# dp_linistepper_v1_0.net
KiCad netlist of a schematic drawn in EAGLE
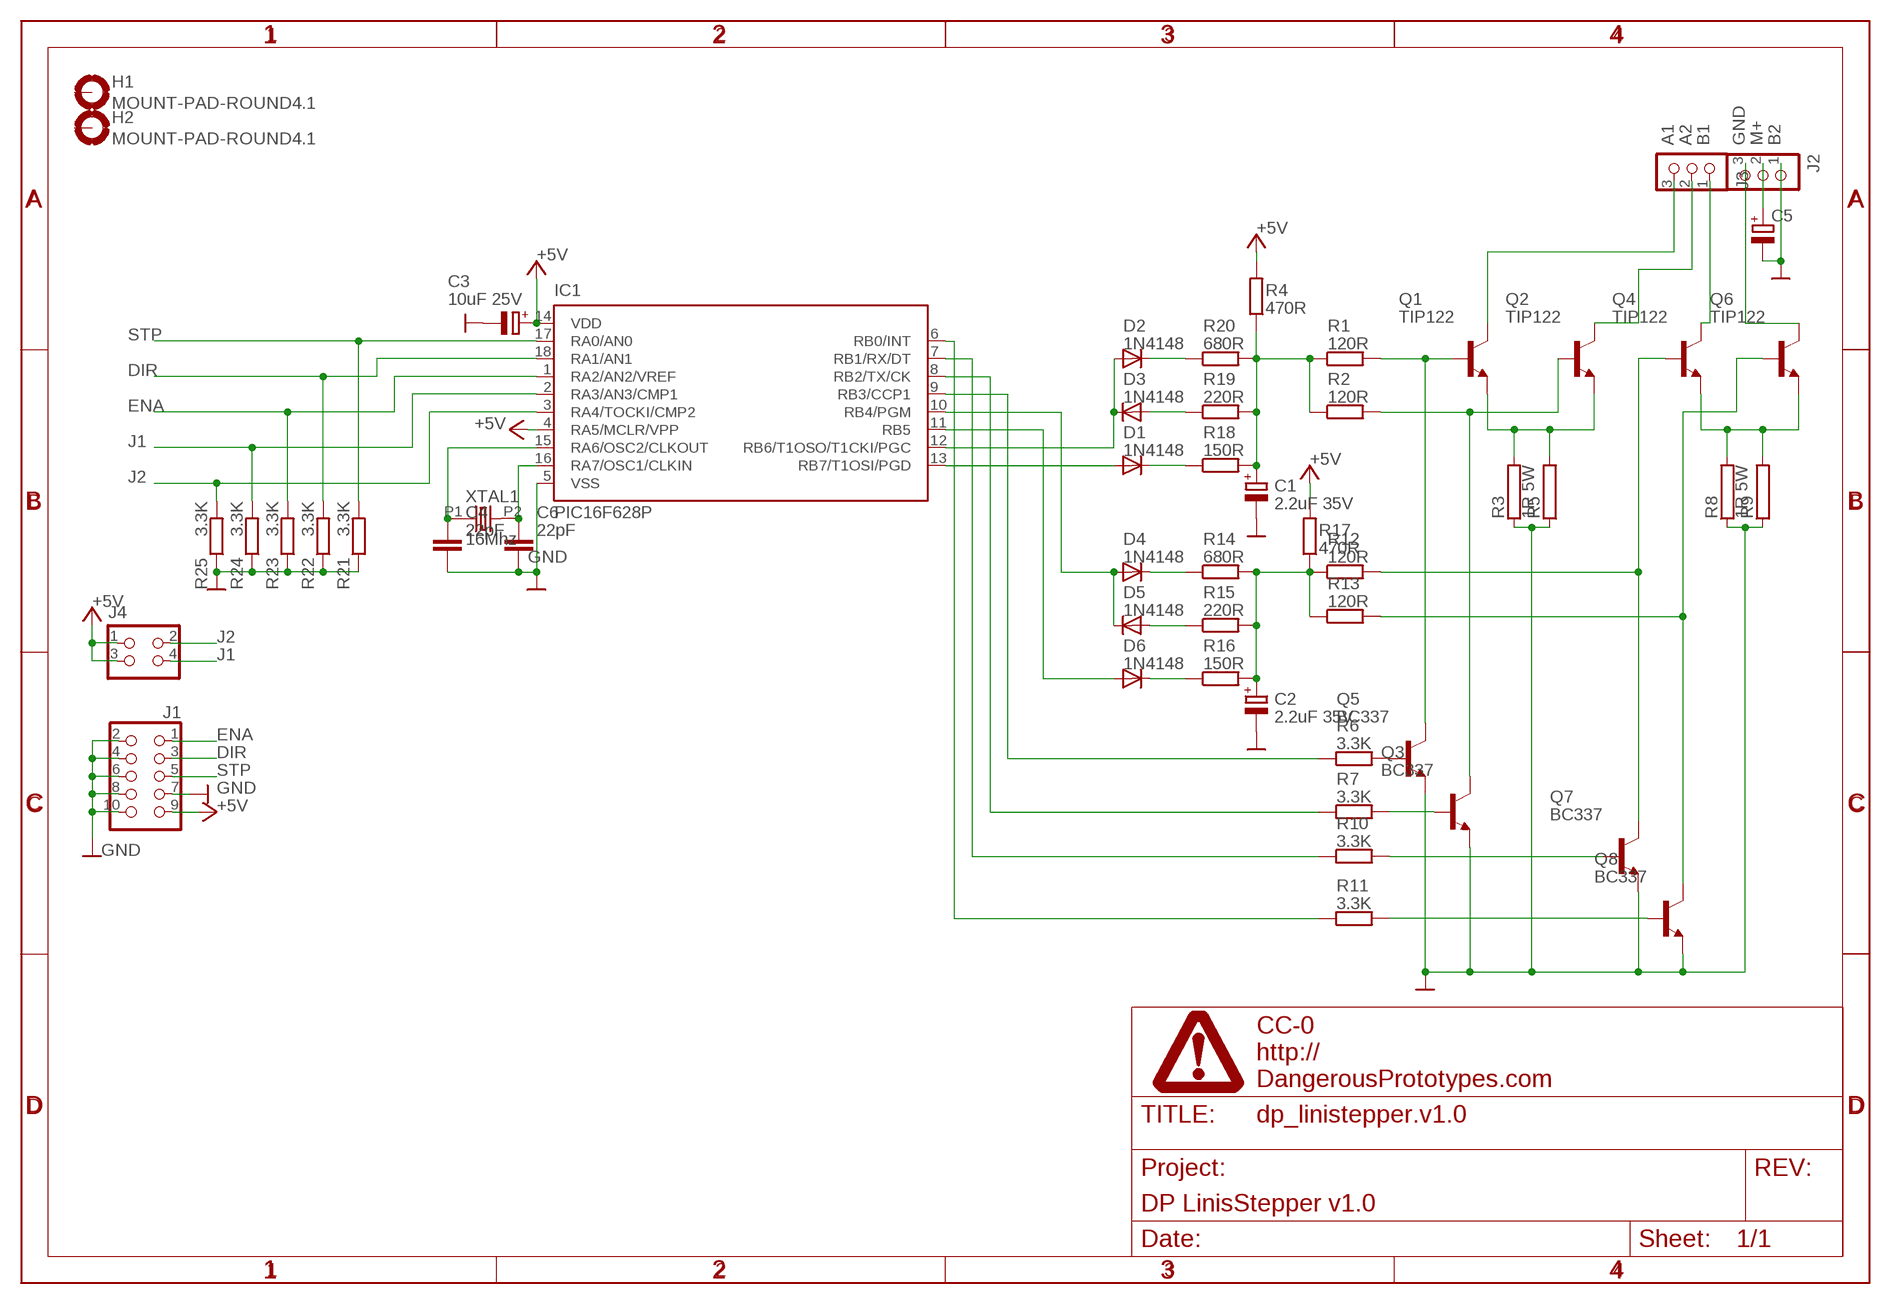
[diagram p0: schematic, sheet 1]

(export (version "E")
  (design (tool "Eeschema 10.0.6"))
  (components
    (comp (ref "C1")
      (value "2.2uF 35V")
      (footprint "eagle-import:ETR1")
      (libsource (lib "eagle-import") (part "CPOL-EUETR1"))
    )
    (comp (ref "C2")
      (value "2.2uF 35V")
      (footprint "eagle-import:ETR1")
      (libsource (lib "eagle-import") (part "CPOL-EUETR1"))
    )
    (comp (ref "C3")
      (value "10uF 25V")
      (footprint "eagle-import:ETR1")
      (libsource (lib "eagle-import") (part "CPOL-EUETR1"))
    )
    (comp (ref "C4")
      (value "22pF")
      (footprint "eagle-import:C0.1PTH")
      (libsource (lib "eagle-import") (part "CAPACITOR_NPOL-PTH_0.1{dblquote}"))
    )
    (comp (ref "C5")
      (value "CPOL-EUE5-13")
      (footprint "eagle-import:E5-13")
      (libsource (lib "eagle-import") (part "CPOL-EUE5-13"))
    )
    (comp (ref "C6")
      (value "22pF")
      (footprint "eagle-import:C0.1PTH")
      (libsource (lib "eagle-import") (part "CAPACITOR_NPOL-PTH_0.1{dblquote}"))
    )
    (comp (ref "D1")
      (value "1N4148")
      (footprint "eagle-import:DO35-10")
      (libsource (lib "eagle-import") (part "1N4148"))
    )
    (comp (ref "D2")
      (value "1N4148")
      (footprint "eagle-import:DO35-10")
      (libsource (lib "eagle-import") (part "1N4148"))
    )
    (comp (ref "D3")
      (value "1N4148")
      (footprint "eagle-import:DO35-10")
      (libsource (lib "eagle-import") (part "1N4148"))
    )
    (comp (ref "D4")
      (value "1N4148")
      (footprint "eagle-import:DO35-10")
      (libsource (lib "eagle-import") (part "1N4148"))
    )
    (comp (ref "D5")
      (value "1N4148")
      (footprint "eagle-import:DO35-10")
      (libsource (lib "eagle-import") (part "1N4148"))
    )
    (comp (ref "D6")
      (value "1N4148")
      (footprint "eagle-import:DO35-10")
      (libsource (lib "eagle-import") (part "1N4148"))
    )
    (comp (ref "H1")
      (value "MOUNT-PAD-ROUND4.1")
      (footprint "eagle-import:4,1-PAD")
      (libsource (lib "eagle-import") (part "MOUNT-PAD-ROUND4.1"))
    )
    (comp (ref "H2")
      (value "MOUNT-PAD-ROUND4.1")
      (footprint "eagle-import:4,1-PAD")
      (libsource (lib "eagle-import") (part "MOUNT-PAD-ROUND4.1"))
    )
    (comp (ref "IC1")
      (value "PIC16F628P")
      (footprint "eagle-import:DIL18")
      (fields (field (name "MF") "MICROCHIP") (field (name "MPN") "PIC16F628-04I/P"))
      (libsource (lib "eagle-import") (part "PIC16F62P8"))
    )
    (comp (ref "J1")
      (value "CON_HEADER_2X05-PTH")
      (footprint "eagle-import:M2X5")
      (libsource (lib "eagle-import") (part "CON_HEADER_2X05-PTH"))
    )
    (comp (ref "J2")
      (value "CON_TERMINAL_BLOCK_03-5MM")
      (footprint "eagle-import:TERMINAL_BLOCK_3P_5")
      (libsource (lib "eagle-import") (part "CON_TERMINAL_BLOCK_03-5MM"))
    )
    (comp (ref "J3")
      (value "CON_TERMINAL_BLOCK_03-5MM")
      (footprint "eagle-import:TERMINAL_BLOCK_3P_5")
      (libsource (lib "eagle-import") (part "CON_TERMINAL_BLOCK_03-5MM"))
    )
    (comp (ref "J4")
      (value "CON_HEADER_2X02-PTH")
      (footprint "eagle-import:M2X2")
      (libsource (lib "eagle-import") (part "CON_HEADER_2X02-PTH"))
    )
    (comp (ref "Q1")
      (value "TIP122")
      (footprint "eagle-import:TO220AV")
      (libsource (lib "eagle-import") (part "2SC2098V"))
    )
    (comp (ref "Q2")
      (value "TIP122")
      (footprint "eagle-import:TO220AV")
      (libsource (lib "eagle-import") (part "2SC2098V"))
    )
    (comp (ref "Q3")
      (value "BC337")
      (footprint "eagle-import:TO92")
      (libsource (lib "eagle-import") (part "BC337"))
    )
    (comp (ref "Q4")
      (value "TIP122")
      (footprint "eagle-import:TO220AV")
      (libsource (lib "eagle-import") (part "2SC2098V"))
    )
    (comp (ref "Q5")
      (value "BC337")
      (footprint "eagle-import:TO92")
      (libsource (lib "eagle-import") (part "BC337"))
    )
    (comp (ref "Q6")
      (value "TIP122")
      (footprint "eagle-import:TO220AV")
      (libsource (lib "eagle-import") (part "2SC2098V"))
    )
    (comp (ref "Q7")
      (value "BC337")
      (footprint "eagle-import:TO92")
      (libsource (lib "eagle-import") (part "BC337"))
    )
    (comp (ref "Q8")
      (value "BC337")
      (footprint "eagle-import:TO92")
      (libsource (lib "eagle-import") (part "BC337"))
    )
    (comp (ref "R1")
      (value "120R")
      (footprint "eagle-import:RTH025W")
      (libsource (lib "eagle-import") (part "RESISTOR-PTH-0.4"))
    )
    (comp (ref "R2")
      (value "120R")
      (footprint "eagle-import:RTH025W")
      (libsource (lib "eagle-import") (part "RESISTOR-PTH-0.4"))
    )
    (comp (ref "R3")
      (value "1R 5W")
      (footprint "eagle-import:HPS923")
      (libsource (lib "eagle-import") (part "RHPS923"))
    )
    (comp (ref "R4")
      (value "470R")
      (footprint "eagle-import:RTH025W")
      (libsource (lib "eagle-import") (part "RESISTOR-PTH-0.4"))
    )
    (comp (ref "R5")
      (value "RHPS63")
      (footprint "eagle-import:HPS63")
      (libsource (lib "eagle-import") (part "RHPS63"))
    )
    (comp (ref "R6")
      (value "3.3K")
      (footprint "eagle-import:RTH025W")
      (libsource (lib "eagle-import") (part "RESISTOR-PTH-0.4"))
    )
    (comp (ref "R7")
      (value "3.3K")
      (footprint "eagle-import:RTH025W")
      (libsource (lib "eagle-import") (part "RESISTOR-PTH-0.4"))
    )
    (comp (ref "R8")
      (value "1R 5W")
      (footprint "eagle-import:HPS923")
      (fields (field (name "OC_FARNELL") "unknown") (field (name "OC_NEWARK") "unknown"))
      (libsource (lib "eagle-import") (part "RHPS923"))
    )
    (comp (ref "R9")
      (value "RHPS63")
      (footprint "eagle-import:HPS63")
      (fields (field (name "OC_FARNELL") "unknown") (field (name "OC_NEWARK") "unknown"))
      (libsource (lib "eagle-import") (part "RHPS63"))
    )
    (comp (ref "R10")
      (value "3.3K")
      (footprint "eagle-import:RTH025W")
      (libsource (lib "eagle-import") (part "RESISTOR-PTH-0.4"))
    )
    (comp (ref "R11")
      (value "3.3K")
      (footprint "eagle-import:RTH025W")
      (libsource (lib "eagle-import") (part "RESISTOR-PTH-0.4"))
    )
    (comp (ref "R12")
      (value "120R")
      (footprint "eagle-import:RTH025W")
      (libsource (lib "eagle-import") (part "RESISTOR-PTH-0.4"))
    )
    (comp (ref "R13")
      (value "120R")
      (footprint "eagle-import:RTH025W")
      (libsource (lib "eagle-import") (part "RESISTOR-PTH-0.4"))
    )
    (comp (ref "R14")
      (value "680R")
      (footprint "eagle-import:RTH025W")
      (libsource (lib "eagle-import") (part "RESISTOR-PTH-0.4"))
    )
    (comp (ref "R15")
      (value "220R")
      (footprint "eagle-import:RTH025W")
      (libsource (lib "eagle-import") (part "RESISTOR-PTH-0.4"))
    )
    (comp (ref "R16")
      (value "150R")
      (footprint "eagle-import:RTH025W")
      (libsource (lib "eagle-import") (part "RESISTOR-PTH-0.4"))
    )
    (comp (ref "R17")
      (value "470R")
      (footprint "eagle-import:RTH025W")
      (libsource (lib "eagle-import") (part "RESISTOR-PTH-0.4"))
    )
    (comp (ref "R18")
      (value "150R")
      (footprint "eagle-import:RTH025W")
      (libsource (lib "eagle-import") (part "RESISTOR-PTH-0.4"))
    )
    (comp (ref "R19")
      (value "220R")
      (footprint "eagle-import:RTH025W")
      (libsource (lib "eagle-import") (part "RESISTOR-PTH-0.4"))
    )
    (comp (ref "R20")
      (value "680R")
      (footprint "eagle-import:RTH025W")
      (libsource (lib "eagle-import") (part "RESISTOR-PTH-0.4"))
    )
    (comp (ref "R21")
      (value "3.3K")
      (footprint "eagle-import:RTH025W")
      (libsource (lib "eagle-import") (part "RESISTOR-PTH-0.4"))
    )
    (comp (ref "R22")
      (value "3.3K")
      (footprint "eagle-import:RTH025W")
      (libsource (lib "eagle-import") (part "RESISTOR-PTH-0.4"))
    )
    (comp (ref "R23")
      (value "3.3K")
      (footprint "eagle-import:RTH025W")
      (libsource (lib "eagle-import") (part "RESISTOR-PTH-0.4"))
    )
    (comp (ref "R24")
      (value "3.3K")
      (footprint "eagle-import:RTH025W")
      (libsource (lib "eagle-import") (part "RESISTOR-PTH-0.4"))
    )
    (comp (ref "R25")
      (value "3.3K")
      (footprint "eagle-import:RTH025W")
      (libsource (lib "eagle-import") (part "RESISTOR-PTH-0.4"))
    )
    (comp (ref "U$1")
      (value "FRAME_DINA4_L")
      (footprint "eagle-import:DP_LOGO")
      (fields (field (name "LICENSE") "CC-0") (field (name "PROJECT") "DP LinisStepper v1.0"))
      (libsource (lib "eagle-import") (part "FRAME_DINA4_L"))
    )
    (comp (ref "XTAL1")
      (value "16Mhz")
      (footprint "eagle-import:HC-49U-PTH")
      (libsource (lib "eagle-import") (part "OSC-XTAL-HC-49U-PTH"))
    )
  )
  (nets
    (net (code "1") (name "/A1") (class "Default")
      (node (ref "J3") (pin "3") (pinfunction "3_3") (pintype "bidirectional"))
      (node (ref "Q1") (pin "2") (pinfunction "C_2") (pintype "passive"))
    )
    (net (code "2") (name "/A2") (class "Default")
      (node (ref "J3") (pin "2") (pinfunction "2_2") (pintype "bidirectional"))
      (node (ref "Q2") (pin "2") (pinfunction "C_2") (pintype "passive"))
    )
    (net (code "3") (name "/B1") (class "Default")
      (node (ref "J3") (pin "1") (pinfunction "1_1") (pintype "bidirectional"))
      (node (ref "Q4") (pin "2") (pinfunction "C_2") (pintype "passive"))
    )
    (net (code "4") (name "/B2") (class "Default")
      (node (ref "J2") (pin "3") (pinfunction "3_3") (pintype "bidirectional"))
      (node (ref "Q6") (pin "2") (pinfunction "C_2") (pintype "passive"))
    )
    (net (code "5") (name "/DIR") (class "Default")
      (node (ref "IC1") (pin "18") (pinfunction "RA1/AN1_18") (pintype "bidirectional"))
      (node (ref "J1") (pin "3") (pinfunction "3_3") (pintype "passive"))
      (node (ref "R22") (pin "2") (pinfunction "2_2") (pintype "passive"))
    )
    (net (code "6") (name "/ENA") (class "Default")
      (node (ref "IC1") (pin "1") (pinfunction "RA2/AN2/VREF_1") (pintype "bidirectional"))
      (node (ref "J1") (pin "1") (pinfunction "1_1") (pintype "passive"))
      (node (ref "R23") (pin "2") (pinfunction "2_2") (pintype "passive"))
    )
    (net (code "7") (name "/J1") (class "Default")
      (node (ref "IC1") (pin "2") (pinfunction "RA3/AN3/CMP1_2") (pintype "bidirectional"))
      (node (ref "J4") (pin "4") (pinfunction "4_4") (pintype "passive"))
      (node (ref "R24") (pin "2") (pinfunction "2_2") (pintype "passive"))
    )
    (net (code "8") (name "/J2") (class "Default")
      (node (ref "IC1") (pin "3") (pinfunction "RA4/TOCKI/CMP2_3") (pintype "bidirectional"))
      (node (ref "J4") (pin "2") (pinfunction "2_2") (pintype "passive"))
      (node (ref "R25") (pin "2") (pinfunction "2_2") (pintype "passive"))
    )
    (net (code "9") (name "/M+") (class "Default")
      (node (ref "C5") (pin "+") (pinfunction "+_+") (pintype "passive"))
      (node (ref "J2") (pin "2") (pinfunction "2_2") (pintype "bidirectional"))
    )
    (net (code "10") (name "/STP") (class "Default")
      (node (ref "IC1") (pin "17") (pinfunction "RA0/AN0_17") (pintype "bidirectional"))
      (node (ref "J1") (pin "5") (pinfunction "5_5") (pintype "passive"))
      (node (ref "R21") (pin "2") (pinfunction "2_2") (pintype "passive"))
    )
    (net (code "11") (name "Net-(C1-Pad+)") (class "Default")
      (node (ref "C1") (pin "+") (pinfunction "+_+") (pintype "passive"))
      (node (ref "R1") (pin "1") (pinfunction "1_1") (pintype "passive"))
      (node (ref "R18") (pin "2") (pinfunction "2_2") (pintype "passive"))
      (node (ref "R19") (pin "2") (pinfunction "2_2") (pintype "passive"))
      (node (ref "R2") (pin "1") (pinfunction "1_1") (pintype "passive"))
      (node (ref "R20") (pin "2") (pinfunction "2_2") (pintype "passive"))
      (node (ref "R4") (pin "1") (pinfunction "1_1") (pintype "passive"))
    )
    (net (code "12") (name "Net-(C2-Pad+)") (class "Default")
      (node (ref "C2") (pin "+") (pinfunction "+_+") (pintype "passive"))
      (node (ref "R12") (pin "1") (pinfunction "1_1") (pintype "passive"))
      (node (ref "R13") (pin "1") (pinfunction "1_1") (pintype "passive"))
      (node (ref "R14") (pin "2") (pinfunction "2_2") (pintype "passive"))
      (node (ref "R15") (pin "2") (pinfunction "2_2") (pintype "passive"))
      (node (ref "R16") (pin "2") (pinfunction "2_2") (pintype "passive"))
      (node (ref "R17") (pin "1") (pinfunction "1_1") (pintype "passive"))
    )
    (net (code "13") (name "Net-(D1-PadC)") (class "Default")
      (node (ref "D1") (pin "C") (pinfunction "C_C") (pintype "passive"))
      (node (ref "R18") (pin "1") (pinfunction "1_1") (pintype "passive"))
    )
    (net (code "14") (name "Net-(D2-PadC)") (class "Default")
      (node (ref "D2") (pin "C") (pinfunction "C_C") (pintype "passive"))
      (node (ref "R20") (pin "1") (pinfunction "1_1") (pintype "passive"))
    )
    (net (code "15") (name "Net-(D3-PadA)") (class "Default")
      (node (ref "D3") (pin "A") (pinfunction "A_A") (pintype "passive"))
      (node (ref "R19") (pin "1") (pinfunction "1_1") (pintype "passive"))
    )
    (net (code "16") (name "Net-(D4-PadC)") (class "Default")
      (node (ref "D4") (pin "C") (pinfunction "C_C") (pintype "passive"))
      (node (ref "R14") (pin "1") (pinfunction "1_1") (pintype "passive"))
    )
    (net (code "17") (name "Net-(D5-PadA)") (class "Default")
      (node (ref "D5") (pin "A") (pinfunction "A_A") (pintype "passive"))
      (node (ref "R15") (pin "1") (pinfunction "1_1") (pintype "passive"))
    )
    (net (code "18") (name "Net-(D6-PadC)") (class "Default")
      (node (ref "D6") (pin "C") (pinfunction "C_C") (pintype "passive"))
      (node (ref "R16") (pin "1") (pinfunction "1_1") (pintype "passive"))
    )
    (net (code "19") (name "Net-(IC1-RA6{slash}OSC2{slash}CLKOUT)") (class "Default")
      (node (ref "C4") (pin "1") (pinfunction "1_1") (pintype "passive"))
      (node (ref "IC1") (pin "15") (pinfunction "RA6/OSC2/CLKOUT_15") (pintype "bidirectional"))
      (node (ref "XTAL1") (pin "P1") (pinfunction "1_P1") (pintype "passive"))
    )
    (net (code "20") (name "Net-(IC1-RA7{slash}OSC1{slash}CLKIN)") (class "Default")
      (node (ref "C6") (pin "1") (pinfunction "1_1") (pintype "passive"))
      (node (ref "IC1") (pin "16") (pinfunction "RA7/OSC1/CLKIN_16") (pintype "bidirectional"))
      (node (ref "XTAL1") (pin "P2") (pinfunction "2_P2") (pintype "passive"))
    )
    (net (code "21") (name "Net-(IC1-RB0{slash}INT)") (class "Default")
      (node (ref "IC1") (pin "6") (pinfunction "RB0/INT_6") (pintype "bidirectional"))
      (node (ref "R11") (pin "1") (pinfunction "1_1") (pintype "passive"))
    )
    (net (code "22") (name "Net-(IC1-RB1{slash}RX{slash}DT)") (class "Default")
      (node (ref "IC1") (pin "7") (pinfunction "RB1/RX/DT_7") (pintype "bidirectional"))
      (node (ref "R10") (pin "1") (pinfunction "1_1") (pintype "passive"))
    )
    (net (code "23") (name "Net-(IC1-RB2{slash}TX{slash}CK)") (class "Default")
      (node (ref "IC1") (pin "8") (pinfunction "RB2/TX/CK_8") (pintype "bidirectional"))
      (node (ref "R7") (pin "1") (pinfunction "1_1") (pintype "passive"))
    )
    (net (code "24") (name "Net-(IC1-RB3{slash}CCP1)") (class "Default")
      (node (ref "IC1") (pin "9") (pinfunction "RB3/CCP1_9") (pintype "bidirectional"))
      (node (ref "R6") (pin "1") (pinfunction "1_1") (pintype "passive"))
    )
    (net (code "25") (name "Net-(IC1-RB4{slash}PGM)") (class "Default")
      (node (ref "D4") (pin "A") (pinfunction "A_A") (pintype "passive"))
      (node (ref "D5") (pin "C") (pinfunction "C_C") (pintype "passive"))
      (node (ref "IC1") (pin "10") (pinfunction "RB4/PGM_10") (pintype "bidirectional"))
    )
    (net (code "26") (name "Net-(IC1-RB5)") (class "Default")
      (node (ref "D6") (pin "A") (pinfunction "A_A") (pintype "passive"))
      (node (ref "IC1") (pin "11") (pinfunction "RB5_11") (pintype "bidirectional"))
    )
    (net (code "27") (name "Net-(IC1-RB6{slash}T1OSO{slash}T1CKI{slash}PGC)") (class "Default")
      (node (ref "D2") (pin "A") (pinfunction "A_A") (pintype "passive"))
      (node (ref "D3") (pin "C") (pinfunction "C_C") (pintype "passive"))
      (node (ref "IC1") (pin "12") (pinfunction "RB6/T1OSO/T1CKI/PGC_12") (pintype "bidirectional"))
    )
    (net (code "28") (name "Net-(IC1-RB7{slash}T1OSI{slash}PGD)") (class "Default")
      (node (ref "D1") (pin "A") (pinfunction "A_A") (pintype "passive"))
      (node (ref "IC1") (pin "13") (pinfunction "RB7/T1OSI/PGD_13") (pintype "bidirectional"))
    )
    (net (code "29") (name "Net-(Q1-B)") (class "Default")
      (node (ref "Q1") (pin "1") (pinfunction "B_1") (pintype "passive"))
      (node (ref "Q5") (pin "3") (pinfunction "C_3") (pintype "passive"))
      (node (ref "R1") (pin "2") (pinfunction "2_2") (pintype "passive"))
    )
    (net (code "30") (name "Net-(Q1-E)") (class "Default")
      (node (ref "Q1") (pin "3") (pinfunction "E_3") (pintype "passive"))
      (node (ref "Q2") (pin "3") (pinfunction "E_3") (pintype "passive"))
      (node (ref "R3") (pin "2") (pinfunction "2_2") (pintype "passive"))
      (node (ref "R5") (pin "2") (pinfunction "2_2") (pintype "passive"))
    )
    (net (code "31") (name "Net-(Q2-B)") (class "Default")
      (node (ref "Q2") (pin "1") (pinfunction "B_1") (pintype "passive"))
      (node (ref "Q3") (pin "3") (pinfunction "C_3") (pintype "passive"))
      (node (ref "R2") (pin "2") (pinfunction "2_2") (pintype "passive"))
    )
    (net (code "32") (name "Net-(Q3-B)") (class "Default")
      (node (ref "Q3") (pin "2") (pinfunction "B_2") (pintype "passive"))
      (node (ref "R7") (pin "2") (pinfunction "2_2") (pintype "passive"))
    )
    (net (code "33") (name "Net-(Q4-B)") (class "Default")
      (node (ref "Q4") (pin "1") (pinfunction "B_1") (pintype "passive"))
      (node (ref "Q7") (pin "3") (pinfunction "C_3") (pintype "passive"))
      (node (ref "R12") (pin "2") (pinfunction "2_2") (pintype "passive"))
    )
    (net (code "34") (name "Net-(Q4-E)") (class "Default")
      (node (ref "Q4") (pin "3") (pinfunction "E_3") (pintype "passive"))
      (node (ref "Q6") (pin "3") (pinfunction "E_3") (pintype "passive"))
      (node (ref "R8") (pin "2") (pinfunction "2_2") (pintype "passive"))
      (node (ref "R9") (pin "2") (pinfunction "2_2") (pintype "passive"))
    )
    (net (code "35") (name "Net-(Q5-B)") (class "Default")
      (node (ref "Q5") (pin "2") (pinfunction "B_2") (pintype "passive"))
      (node (ref "R6") (pin "2") (pinfunction "2_2") (pintype "passive"))
    )
    (net (code "36") (name "Net-(Q6-B)") (class "Default")
      (node (ref "Q6") (pin "1") (pinfunction "B_1") (pintype "passive"))
      (node (ref "Q8") (pin "3") (pinfunction "C_3") (pintype "passive"))
      (node (ref "R13") (pin "2") (pinfunction "2_2") (pintype "passive"))
    )
    (net (code "37") (name "Net-(Q7-B)") (class "Default")
      (node (ref "Q7") (pin "2") (pinfunction "B_2") (pintype "passive"))
      (node (ref "R10") (pin "2") (pinfunction "2_2") (pintype "passive"))
    )
    (net (code "38") (name "Net-(Q8-B)") (class "Default")
      (node (ref "Q8") (pin "2") (pinfunction "B_2") (pintype "passive"))
      (node (ref "R11") (pin "2") (pinfunction "2_2") (pintype "passive"))
    )
    (net (code "39") (name "SUPPLY_+5V") (class "Default")
      (node (ref "C3") (pin "+") (pinfunction "+_+") (pintype "passive"))
      (node (ref "IC1") (pin "14") (pinfunction "VDD_14") (pintype "power_in"))
      (node (ref "IC1") (pin "4") (pinfunction "RA5/MCLR/VPP_4") (pintype "bidirectional"))
      (node (ref "J1") (pin "9") (pinfunction "9_9") (pintype "passive"))
      (node (ref "J4") (pin "1") (pinfunction "1_1") (pintype "passive"))
      (node (ref "J4") (pin "3") (pinfunction "3_3") (pintype "passive"))
      (node (ref "R17") (pin "2") (pinfunction "2_2") (pintype "passive"))
      (node (ref "R4") (pin "2") (pinfunction "2_2") (pintype "passive"))
    )
    (net (code "40") (name "SUPPLY_GND") (class "Default")
      (node (ref "C1") (pin "-") (pinfunction "-_-") (pintype "passive"))
      (node (ref "C2") (pin "-") (pinfunction "-_-") (pintype "passive"))
      (node (ref "C3") (pin "-") (pinfunction "-_-") (pintype "passive"))
      (node (ref "C4") (pin "2") (pinfunction "2_2") (pintype "passive"))
      (node (ref "C5") (pin "-") (pinfunction "-_-") (pintype "passive"))
      (node (ref "C6") (pin "2") (pinfunction "2_2") (pintype "passive"))
      (node (ref "IC1") (pin "5") (pinfunction "VSS_5") (pintype "power_in"))
      (node (ref "J1") (pin "10") (pinfunction "10_10") (pintype "passive"))
      (node (ref "J1") (pin "2") (pinfunction "2_2") (pintype "passive"))
      (node (ref "J1") (pin "4") (pinfunction "4_4") (pintype "passive"))
      (node (ref "J1") (pin "6") (pinfunction "6_6") (pintype "passive"))
      (node (ref "J1") (pin "7") (pinfunction "7_7") (pintype "passive"))
      (node (ref "J1") (pin "8") (pinfunction "8_8") (pintype "passive"))
      (node (ref "J2") (pin "1") (pinfunction "1_1") (pintype "bidirectional"))
      (node (ref "Q3") (pin "1") (pinfunction "E_1") (pintype "passive"))
      (node (ref "Q5") (pin "1") (pinfunction "E_1") (pintype "passive"))
      (node (ref "Q7") (pin "1") (pinfunction "E_1") (pintype "passive"))
      (node (ref "Q8") (pin "1") (pinfunction "E_1") (pintype "passive"))
      (node (ref "R21") (pin "1") (pinfunction "1_1") (pintype "passive"))
      (node (ref "R22") (pin "1") (pinfunction "1_1") (pintype "passive"))
      (node (ref "R23") (pin "1") (pinfunction "1_1") (pintype "passive"))
      (node (ref "R24") (pin "1") (pinfunction "1_1") (pintype "passive"))
      (node (ref "R25") (pin "1") (pinfunction "1_1") (pintype "passive"))
      (node (ref "R3") (pin "1") (pinfunction "1_1") (pintype "passive"))
      (node (ref "R5") (pin "1") (pinfunction "1_1") (pintype "passive"))
      (node (ref "R8") (pin "1") (pinfunction "1_1") (pintype "passive"))
      (node (ref "R9") (pin "1") (pinfunction "1_1") (pintype "passive"))
    )
    (net (code "41") (name "unconnected-(H1-MOUNT-PadB4,1)") (class "Default")
      (node (ref "H1") (pin "B4,1") (pinfunction "MOUNT_B4,1") (pintype "passive"))
    )
    (net (code "42") (name "unconnected-(H2-MOUNT-PadB4,1)") (class "Default")
      (node (ref "H2") (pin "B4,1") (pinfunction "MOUNT_B4,1") (pintype "passive"))
    )
  )
)
